# C12880-vertical.net
KiCad netlist of a schematic drawn in EAGLE
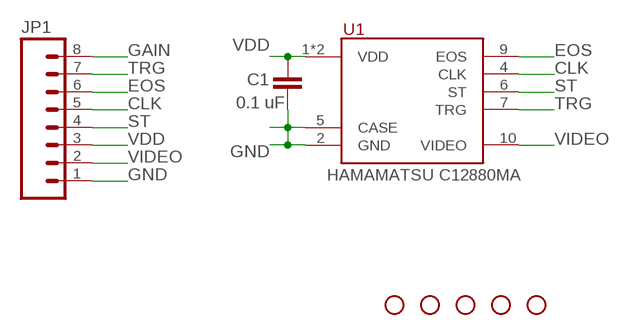
[diagram p0: schematic, sheet 1]

(export (version "E")
  (design (tool "Eeschema 10.0.6"))
  (components
    (comp (ref "C1")
      (value "0.1 uF")
      (footprint "eagle-import:C0805")
      (libsource (lib "eagle-import") (part "C-EUC0805"))
    )
    (comp (ref "JP1")
      (value "M08SILK_FEMALE_PTH")
      (footprint "eagle-import:1X08")
      (libsource (lib "eagle-import") (part "M08SILK_FEMALE_PTH"))
    )
    (comp (ref "STANDOFF1")
      (value "STAND-OFF")
      (footprint "eagle-import:STAND-OFF")
      (libsource (lib "eagle-import") (part "STAND-OFF"))
    )
    (comp (ref "STANDOFF2")
      (value "STAND-OFF")
      (footprint "eagle-import:STAND-OFF")
      (libsource (lib "eagle-import") (part "STAND-OFF"))
    )
    (comp (ref "STANDOFF3")
      (value "STAND-OFF")
      (footprint "eagle-import:STAND-OFF")
      (libsource (lib "eagle-import") (part "STAND-OFF"))
    )
    (comp (ref "STANDOFF4")
      (value "STAND-OFF")
      (footprint "eagle-import:STAND-OFF")
      (libsource (lib "eagle-import") (part "STAND-OFF"))
    )
    (comp (ref "STANDOFF5")
      (value "STAND-OFF")
      (footprint "eagle-import:STAND-OFF")
      (libsource (lib "eagle-import") (part "STAND-OFF"))
    )
    (comp (ref "U1")
      (value "MICROSPEC-C12880MA")
      (footprint "eagle-import:C12880MA")
      (libsource (lib "eagle-import") (part "MICROSPEC-C12880MA"))
    )
  )
  (nets
    (net (code "1") (name "/CLK") (class "Default")
      (node (ref "JP1") (pin "5") (pinfunction "5_5") (pintype "passive"))
      (node (ref "U1") (pin "4") (pinfunction "CLK_4") (pintype "bidirectional"))
    )
    (net (code "2") (name "/EOS") (class "Default")
      (node (ref "JP1") (pin "6") (pinfunction "6_6") (pintype "passive"))
      (node (ref "U1") (pin "9") (pinfunction "EOS_9") (pintype "bidirectional"))
    )
    (net (code "3") (name "/GAIN") (class "Default")
      (node (ref "JP1") (pin "8") (pinfunction "8_8") (pintype "passive"))
    )
    (net (code "4") (name "/GND") (class "Default")
      (node (ref "C1") (pin "2") (pinfunction "2_2") (pintype "passive"))
      (node (ref "JP1") (pin "1") (pinfunction "1_1") (pintype "passive"))
      (node (ref "U1") (pin "2") (pinfunction "GND_2") (pintype "bidirectional"))
      (node (ref "U1") (pin "5") (pinfunction "CASE_5") (pintype "bidirectional"))
    )
    (net (code "5") (name "/ST") (class "Default")
      (node (ref "JP1") (pin "4") (pinfunction "4_4") (pintype "passive"))
      (node (ref "U1") (pin "6") (pinfunction "ST_6") (pintype "bidirectional"))
    )
    (net (code "6") (name "/TRG") (class "Default")
      (node (ref "JP1") (pin "7") (pinfunction "7_7") (pintype "passive"))
      (node (ref "U1") (pin "7") (pinfunction "TRG_7") (pintype "bidirectional"))
    )
    (net (code "7") (name "/VDD") (class "Default")
      (node (ref "C1") (pin "1") (pinfunction "1_1") (pintype "passive"))
      (node (ref "JP1") (pin "3") (pinfunction "3_3") (pintype "passive"))
      (node (ref "U1") (pin "1") (pinfunction "VDD_1") (pintype "bidirectional"))
      (node (ref "U1") (pin "3") (pinfunction "VDD_3") (pintype "bidirectional"))
    )
    (net (code "8") (name "/VIDEO") (class "Default")
      (node (ref "JP1") (pin "2") (pinfunction "2_2") (pintype "passive"))
      (node (ref "U1") (pin "10") (pinfunction "VIDEO_10") (pintype "bidirectional"))
    )
  )
)
